# ProPrj.net
KiCad netlist of a schematic drawn in EasyEDA Pro
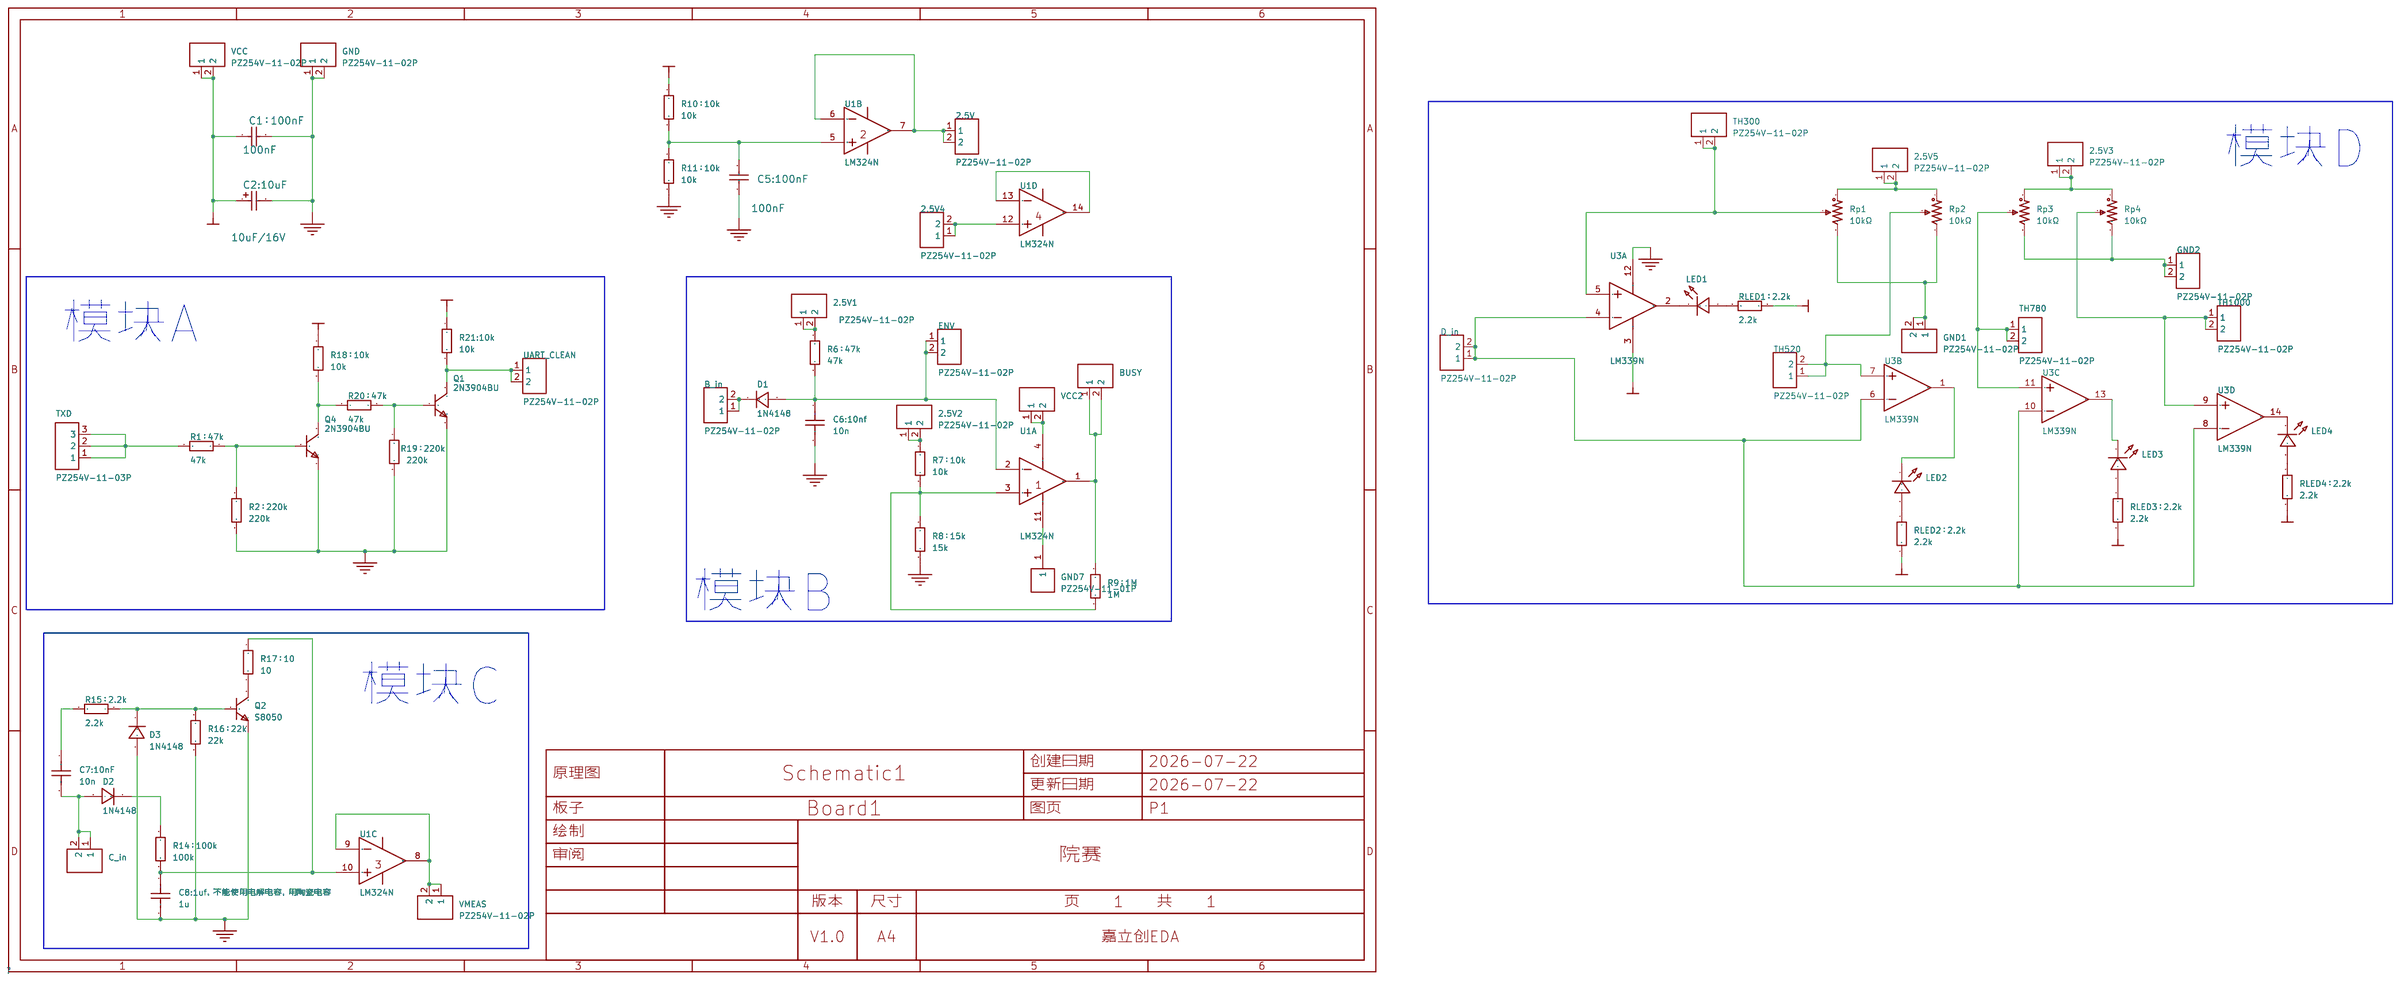
[diagram p0: schematic sheet]

(export (version "E")
  (design (tool "Eeschema 10.0.6"))
  (components
    (comp (ref "2.5V")
      (value "PZ254V-11-02P")
      (footprint "easyedapro:HDR-TH_2P-P2.54-V-M")
      (fields (field (name "Manufacturer") "XFCN(兴飞)"))
      (libsource (lib "easyedapro") (part "PZ254V-11-02P"))
    )
    (comp (ref "2.5V1")
      (value "PZ254V-11-02P")
      (footprint "easyedapro:HDR-TH_2P-P2.54-V-M")
      (fields (field (name "Manufacturer") "XFCN(兴飞)"))
      (libsource (lib "easyedapro") (part "PZ254V-11-02P"))
    )
    (comp (ref "2.5V2")
      (value "PZ254V-11-02P")
      (footprint "easyedapro:HDR-TH_2P-P2.54-V-M")
      (fields (field (name "Manufacturer") "XFCN(兴飞)"))
      (libsource (lib "easyedapro") (part "PZ254V-11-02P"))
    )
    (comp (ref "2.5V3")
      (value "PZ254V-11-02P")
      (footprint "easyedapro:HDR-TH_2P-P2.54-V-M")
      (fields (field (name "Manufacturer") "XFCN(兴飞)"))
      (libsource (lib "easyedapro") (part "PZ254V-11-02P"))
    )
    (comp (ref "2.5V4")
      (value "PZ254V-11-02P")
      (footprint "easyedapro:HDR-TH_2P-P2.54-V-M")
      (fields (field (name "Manufacturer") "XFCN(兴飞)"))
      (libsource (lib "easyedapro") (part "PZ254V-11-02P"))
    )
    (comp (ref "2.5V5")
      (value "PZ254V-11-02P")
      (footprint "easyedapro:HDR-TH_2P-P2.54-V-M")
      (fields (field (name "Manufacturer") "XFCN(兴飞)"))
      (libsource (lib "easyedapro") (part "PZ254V-11-02P"))
    )
    (comp (ref "BUSY")
      (value "PZ254V-11-02P")
      (footprint "easyedapro:HDR-TH_2P-P2.54-V-M")
      (fields (field (name "Manufacturer") "XFCN(兴飞)"))
      (libsource (lib "easyedapro") (part "PZ254V-11-02P"))
    )
    (comp (ref "B_in")
      (value "PZ254V-11-02P")
      (footprint "easyedapro:HDR-TH_2P-P2.54-V-M")
      (fields (field (name "Manufacturer") "XFCN(兴飞)"))
      (libsource (lib "easyedapro") (part "PZ254V-11-02P"))
    )
    (comp (ref "C1：100nF")
      (value "100nF")
      (footprint "easyedapro:0805")
      (description "Capacitor")
      (fields (field (name "Publisher") "Altium Limited"))
      (libsource (lib "easyedapro") (part "Cap"))
    )
    (comp (ref "C2:10uF")
      (value "10uF/16V")
      (footprint "easyedapro:P1210")
      (description "Polarized Capacitor (Radial)")
      (fields (field (name "Publisher") "Altium Limited"))
      (libsource (lib "easyedapro") (part "Cap Pol1"))
    )
    (comp (ref "C5:100nF")
      (value "100nF")
      (footprint "easyedapro:0805")
      (description "Capacitor")
      (fields (field (name "Publisher") "Altium Limited"))
      (libsource (lib "easyedapro") (part "Cap"))
    )
    (comp (ref "C6:10nf")
      (value "10n")
      (footprint "easyedapro:CAP-TH_L8.5-W5.0-P5.00-D1.2")
      (description "容值:100nF;精度:±10%;额定电压:50V;温度系数:X7R;")
      (fields (field (name "Manufacturer Part") "CT4-0805B104K500F3") (field (name "Manufacturer") "FH(风华)"))
      (libsource (lib "easyedapro") (part "CT4-0805B104K500F3"))
    )
    (comp (ref "C7:10nF")
      (value "10n")
      (footprint "easyedapro:CAP-TH_L8.5-W5.0-P5.00-D1.2")
      (description "容值:100nF;精度:±10%;额定电压:50V;温度系数:X7R;")
      (fields (field (name "Manufacturer Part") "CT4-0805B104K500F3") (field (name "Manufacturer") "FH(风华)"))
      (libsource (lib "easyedapro") (part "CT4-0805B104K500F3"))
    )
    (comp (ref "C8:1uf，不能使用电解电容，用陶瓷电容")
      (value "1u")
      (footprint "easyedapro:CAP-TH_L8.5-W5.0-P5.00-D1.2")
      (description "容值:100nF;精度:±10%;额定电压:50V;温度系数:X7R;")
      (fields (field (name "Manufacturer Part") "CT4-0805B104K500F3") (field (name "Manufacturer") "FH(风华)"))
      (libsource (lib "easyedapro") (part "CT4-0805B104K500F3"))
    )
    (comp (ref "C_in")
      (value "PZ254V-11-02P")
      (footprint "easyedapro:HDR-TH_2P-P2.54-V-M")
      (fields (field (name "Manufacturer") "XFCN(兴飞)"))
      (libsource (lib "easyedapro") (part "PZ254V-11-02P"))
    )
    (comp (ref "D1")
      (value "1N4148")
      (footprint "easyedapro:DO-35_BD2.0-L4.2-P8.20-D0.5-RD")
      (description "二极管配置:-;正向压降(Vf):1V@10mA;直流反向耐压(Vr):75V;整流电流:150mA;反向恢复时间(Trr):4ns;")
      (fields (field (name "Manufacturer") "LGE(鲁光)"))
      (libsource (lib "easyedapro") (part "1N4148_C402212"))
    )
    (comp (ref "D2")
      (value "1N4148")
      (footprint "easyedapro:DO-35_BD2.0-L4.2-P8.20-D0.5-RD")
      (description "二极管配置:-;正向压降(Vf):1V@10mA;直流反向耐压(Vr):75V;整流电流:150mA;反向恢复时间(Trr):4ns;")
      (fields (field (name "Manufacturer") "LGE(鲁光)"))
      (libsource (lib "easyedapro") (part "1N4148_C402212"))
    )
    (comp (ref "D3")
      (value "1N4148")
      (footprint "easyedapro:DO-35_BD2.0-L4.2-P8.20-D0.5-RD")
      (description "二极管配置:-;正向压降(Vf):1V@10mA;直流反向耐压(Vr):75V;整流电流:150mA;反向恢复时间(Trr):4ns;")
      (fields (field (name "Manufacturer") "LGE(鲁光)"))
      (libsource (lib "easyedapro") (part "1N4148_C402212"))
    )
    (comp (ref "D_in")
      (value "PZ254V-11-02P")
      (footprint "easyedapro:HDR-TH_2P-P2.54-V-M")
      (fields (field (name "Manufacturer") "XFCN(兴飞)"))
      (libsource (lib "easyedapro") (part "PZ254V-11-02P"))
    )
    (comp (ref "ENV")
      (value "PZ254V-11-02P")
      (footprint "easyedapro:HDR-TH_2P-P2.54-V-M")
      (fields (field (name "Manufacturer") "XFCN(兴飞)"))
      (libsource (lib "easyedapro") (part "PZ254V-11-02P"))
    )
    (comp (ref "GND")
      (value "PZ254V-11-02P")
      (footprint "easyedapro:HDR-TH_2P-P2.54-V-M")
      (fields (field (name "Manufacturer") "XFCN(兴飞)"))
      (libsource (lib "easyedapro") (part "PZ254V-11-02P"))
    )
    (comp (ref "GND1")
      (value "PZ254V-11-02P")
      (footprint "easyedapro:HDR-TH_2P-P2.54-V-M")
      (fields (field (name "Manufacturer") "XFCN(兴飞)"))
      (libsource (lib "easyedapro") (part "PZ254V-11-02P"))
    )
    (comp (ref "GND2")
      (value "PZ254V-11-02P")
      (footprint "easyedapro:HDR-TH_2P-P2.54-V-M")
      (fields (field (name "Manufacturer") "XFCN(兴飞)"))
      (libsource (lib "easyedapro") (part "PZ254V-11-02P"))
    )
    (comp (ref "GND7")
      (value "PZ254V-11-01P")
      (footprint "easyedapro:HDR-TH_1P-P2.54-V-M")
      (fields (field (name "Manufacturer") "XFCN(兴飞)"))
      (libsource (lib "easyedapro") (part "PZ254V-11-01P"))
    )
    (comp (ref "LED1")
      (value "WP1533BQ/ID")
      (footprint "easyedapro:LED-TH_2P-L13.5-W5.9-P2.54_WP1533BQ")
      (fields (field (name "Manufacturer") "Kingbright"))
      (libsource (lib "easyedapro") (part "WP1533BQ/ID"))
    )
    (comp (ref "LED2")
      (value "WP1533BQ/ID")
      (footprint "easyedapro:LED-TH_2P-L13.5-W5.9-P2.54_WP1533BQ")
      (fields (field (name "Manufacturer") "Kingbright"))
      (libsource (lib "easyedapro") (part "WP1533BQ/ID"))
    )
    (comp (ref "LED3")
      (value "WP1533BQ/ID")
      (footprint "easyedapro:LED-TH_2P-L13.5-W5.9-P2.54_WP1533BQ")
      (fields (field (name "Manufacturer") "Kingbright"))
      (libsource (lib "easyedapro") (part "WP1533BQ/ID"))
    )
    (comp (ref "LED4")
      (value "WP1533BQ/ID")
      (footprint "easyedapro:LED-TH_2P-L13.5-W5.9-P2.54_WP1533BQ")
      (fields (field (name "Manufacturer") "Kingbright"))
      (libsource (lib "easyedapro") (part "WP1533BQ/ID"))
    )
    (comp (ref "Q1")
      (value "2N3904BU")
      (footprint "easyedapro:TO-92-3_L5.1-W4.1-P1.27-L")
      (fields (field (name "Manufacturer") "onsemi(安森美)"))
      (libsource (lib "easyedapro") (part "2N3904BU"))
    )
    (comp (ref "Q2")
      (value "S8050")
      (footprint "easyedapro:SOT-23-3_L2.9-W1.3-P1.90-LS2.3-BR")
      (fields (field (name "Manufacturer") "R+O(宏嘉诚)"))
      (libsource (lib "easyedapro") (part "S8050_C20069125"))
    )
    (comp (ref "Q4")
      (value "2N3904BU")
      (footprint "easyedapro:TO-92-3_L5.1-W4.1-P1.27-L")
      (fields (field (name "Manufacturer") "onsemi(安森美)"))
      (libsource (lib "easyedapro") (part "2N3904BU"))
    )
    (comp (ref "R1：47k")
      (value "47k")
      (footprint "easyedapro:R0603")
      (libsource (lib "easyedapro") (part "电阻"))
    )
    (comp (ref "R2：220k")
      (value "220k")
      (footprint "easyedapro:R0603")
      (libsource (lib "easyedapro") (part "电阻"))
    )
    (comp (ref "R6：47k")
      (value "47k")
      (footprint "easyedapro:R0603")
      (libsource (lib "easyedapro") (part "电阻"))
    )
    (comp (ref "R7：10k")
      (value "10k")
      (footprint "easyedapro:R0603")
      (libsource (lib "easyedapro") (part "电阻"))
    )
    (comp (ref "R8：15k")
      (value "15k")
      (footprint "easyedapro:R0603")
      (libsource (lib "easyedapro") (part "电阻"))
    )
    (comp (ref "R9：1M")
      (value "1M")
      (footprint "easyedapro:R0603")
      (libsource (lib "easyedapro") (part "电阻"))
    )
    (comp (ref "R10：10k")
      (value "10k")
      (footprint "easyedapro:R0603")
      (libsource (lib "easyedapro") (part "电阻"))
    )
    (comp (ref "R11：10k")
      (value "10k")
      (footprint "easyedapro:R0603")
      (libsource (lib "easyedapro") (part "电阻"))
    )
    (comp (ref "R14：100k")
      (value "100k")
      (footprint "easyedapro:R0603")
      (libsource (lib "easyedapro") (part "电阻"))
    )
    (comp (ref "R15：2.2k")
      (value "2.2k")
      (footprint "easyedapro:R0603")
      (libsource (lib "easyedapro") (part "电阻"))
    )
    (comp (ref "R16：22k")
      (value "22k")
      (footprint "easyedapro:R0603")
      (libsource (lib "easyedapro") (part "电阻"))
    )
    (comp (ref "R17：10")
      (value "10")
      (footprint "easyedapro:R0603")
      (libsource (lib "easyedapro") (part "电阻"))
    )
    (comp (ref "R18：10k")
      (value "10k")
      (footprint "easyedapro:R0603")
      (libsource (lib "easyedapro") (part "电阻"))
    )
    (comp (ref "R19：220k")
      (value "220k")
      (footprint "easyedapro:R0603")
      (libsource (lib "easyedapro") (part "电阻"))
    )
    (comp (ref "R20：47k")
      (value "47k")
      (footprint "easyedapro:R0603")
      (libsource (lib "easyedapro") (part "电阻"))
    )
    (comp (ref "R21:10k")
      (value "10k")
      (footprint "easyedapro:R0603")
      (libsource (lib "easyedapro") (part "电阻"))
    )
    (comp (ref "RLED1：2.2k")
      (value "2.2k")
      (footprint "easyedapro:R0603")
      (libsource (lib "easyedapro") (part "电阻"))
    )
    (comp (ref "RLED2：2.2k")
      (value "2.2k")
      (footprint "easyedapro:R0603")
      (libsource (lib "easyedapro") (part "电阻"))
    )
    (comp (ref "RLED3：2.2k")
      (value "2.2k")
      (footprint "easyedapro:R0603")
      (libsource (lib "easyedapro") (part "电阻"))
    )
    (comp (ref "RLED4：2.2k")
      (value "2.2k")
      (footprint "easyedapro:R0603")
      (libsource (lib "easyedapro") (part "电阻"))
    )
    (comp (ref "Rp1")
      (value "10kΩ")
      (footprint "easyedapro:RES-ADJ-TH_3P-L10.0-W10.0-P2.50-L")
      (description "阻值:10kΩ;精度:±10%;")
      (fields (field (name "Manufacturer Part") "3296W-1-103") (field (name "Manufacturer") "BOCHEN(博晨)"))
      (libsource (lib "easyedapro") (part "3296W-1-103"))
    )
    (comp (ref "Rp2")
      (value "10kΩ")
      (footprint "easyedapro:RES-ADJ-TH_3P-L10.0-W10.0-P2.50-L")
      (description "阻值:10kΩ;精度:±10%;")
      (fields (field (name "Manufacturer Part") "3296W-1-103") (field (name "Manufacturer") "BOCHEN(博晨)"))
      (libsource (lib "easyedapro") (part "3296W-1-103"))
    )
    (comp (ref "Rp3")
      (value "10kΩ")
      (footprint "easyedapro:RES-ADJ-TH_3P-L10.0-W10.0-P2.50-L")
      (description "阻值:10kΩ;精度:±10%;")
      (fields (field (name "Manufacturer Part") "3296W-1-103") (field (name "Manufacturer") "BOCHEN(博晨)"))
      (libsource (lib "easyedapro") (part "3296W-1-103"))
    )
    (comp (ref "Rp4")
      (value "10kΩ")
      (footprint "easyedapro:RES-ADJ-TH_3P-L10.0-W10.0-P2.50-L")
      (description "阻值:10kΩ;精度:±10%;")
      (fields (field (name "Manufacturer Part") "3296W-1-103") (field (name "Manufacturer") "BOCHEN(博晨)"))
      (libsource (lib "easyedapro") (part "3296W-1-103"))
    )
    (comp (ref "TH300")
      (value "PZ254V-11-02P")
      (footprint "easyedapro:HDR-TH_2P-P2.54-V-M")
      (fields (field (name "Manufacturer") "XFCN(兴飞)"))
      (libsource (lib "easyedapro") (part "PZ254V-11-02P"))
    )
    (comp (ref "TH520")
      (value "PZ254V-11-02P")
      (footprint "easyedapro:HDR-TH_2P-P2.54-V-M")
      (fields (field (name "Manufacturer") "XFCN(兴飞)"))
      (libsource (lib "easyedapro") (part "PZ254V-11-02P"))
    )
    (comp (ref "TH780")
      (value "PZ254V-11-02P")
      (footprint "easyedapro:HDR-TH_2P-P2.54-V-M")
      (fields (field (name "Manufacturer") "XFCN(兴飞)"))
      (libsource (lib "easyedapro") (part "PZ254V-11-02P"))
    )
    (comp (ref "TH1000")
      (value "PZ254V-11-02P")
      (footprint "easyedapro:HDR-TH_2P-P2.54-V-M")
      (fields (field (name "Manufacturer") "XFCN(兴飞)"))
      (libsource (lib "easyedapro") (part "PZ254V-11-02P"))
    )
    (comp (ref "TXD")
      (value "PZ254V-11-03P")
      (footprint "easyedapro:HDR-TH_3P-P2.54-V-M_PZ254V-11-03P")
      (fields (field (name "Manufacturer") "XFCN(兴飞)"))
      (libsource (lib "easyedapro") (part "PZ254V-11-03P_C2937625"))
    )
    (comp (ref "U1")
      (value "LM324N")
      (footprint "easyedapro:DIP-14_L19.4-W6.4-P2.54-LS7.6-BL")
      (fields (field (name "Manufacturer") "HGSEMI(华冠)"))
      (libsource (lib "easyedapro") (part "LM324N_C725320"))
    )
    (comp (ref "U3")
      (value "LM339N")
      (footprint "easyedapro:PDIP-14_L19.3-W6.4-P2.54-LS9.0-BL")
      (fields (field (name "Manufacturer") "TI(德州仪器)"))
      (libsource (lib "easyedapro") (part "LM339N_C39202084"))
    )
    (comp (ref "UART_CLEAN")
      (value "PZ254V-11-02P")
      (footprint "easyedapro:HDR-TH_2P-P2.54-V-M")
      (fields (field (name "Manufacturer") "XFCN(兴飞)"))
      (libsource (lib "easyedapro") (part "PZ254V-11-02P"))
    )
    (comp (ref "VCC")
      (value "PZ254V-11-02P")
      (footprint "easyedapro:HDR-TH_2P-P2.54-V-M")
      (fields (field (name "Manufacturer") "XFCN(兴飞)"))
      (libsource (lib "easyedapro") (part "PZ254V-11-02P"))
    )
    (comp (ref "VCC2")
      (value "PZ254V-11-02P")
      (footprint "easyedapro:HDR-TH_2P-P2.54-V-M")
      (fields (field (name "Manufacturer") "XFCN(兴飞)"))
      (libsource (lib "easyedapro") (part "PZ254V-11-02P"))
    )
    (comp (ref "VMEAS")
      (value "PZ254V-11-02P")
      (footprint "easyedapro:HDR-TH_2P-P2.54-V-M")
      (fields (field (name "Manufacturer") "XFCN(兴飞)"))
      (libsource (lib "easyedapro") (part "PZ254V-11-02P"))
    )
  )
  (nets
    (net (code "1") (name "GND") (class "Default")
      (node (ref "C1：100nF") (pin "2") (pinfunction "2_2") (pintype "unspecified"))
      (node (ref "C2:10uF") (pin "2") (pinfunction "2_2") (pintype "unspecified"))
      (node (ref "C5:100nF") (pin "1") (pinfunction "1_1") (pintype "unspecified"))
      (node (ref "C6:10nf") (pin "2") (pinfunction "2_2") (pintype "unspecified"))
      (node (ref "C8:1uf，不能使用电解电容，用陶瓷电容") (pin "2") (pinfunction "2_2") (pintype "unspecified"))
      (node (ref "D3") (pin "2") (pinfunction "A_2") (pintype "unspecified"))
      (node (ref "GND") (pin "1") (pinfunction "1_1") (pintype "unspecified"))
      (node (ref "GND") (pin "2") (pinfunction "2_2") (pintype "unspecified"))
      (node (ref "Q1") (pin "1") (pinfunction "E_1") (pintype "input"))
      (node (ref "Q2") (pin "2") (pinfunction "E_2") (pintype "input"))
      (node (ref "Q4") (pin "1") (pinfunction "E_1") (pintype "input"))
      (node (ref "R11：10k") (pin "2") (pinfunction "2_2") (pintype "input"))
      (node (ref "R16：22k") (pin "2") (pinfunction "2_2") (pintype "input"))
      (node (ref "R19：220k") (pin "2") (pinfunction "2_2") (pintype "input"))
      (node (ref "R2：220k") (pin "2") (pinfunction "2_2") (pintype "input"))
      (node (ref "R8：15k") (pin "2") (pinfunction "2_2") (pintype "input"))
      (node (ref "U3") (pin "12") (pinfunction "GND_12") (pintype "unspecified"))
    )
    (net (code "2") (name "Net-(2.5V1-Pad1)") (class "Default")
      (node (ref "2.5V1") (pin "1") (pinfunction "1_1") (pintype "unspecified"))
      (node (ref "2.5V1") (pin "2") (pinfunction "2_2") (pintype "unspecified"))
      (node (ref "R6：47k") (pin "1") (pinfunction "1_1") (pintype "input"))
    )
    (net (code "3") (name "Net-(2.5V2-Pad1)") (class "Default")
      (node (ref "2.5V2") (pin "1") (pinfunction "1_1") (pintype "unspecified"))
      (node (ref "2.5V2") (pin "2") (pinfunction "2_2") (pintype "unspecified"))
      (node (ref "R7：10k") (pin "1") (pinfunction "1_1") (pintype "input"))
    )
    (net (code "4") (name "Net-(2.5V3-Pad1)") (class "Default")
      (node (ref "2.5V3") (pin "1") (pinfunction "1_1") (pintype "unspecified"))
      (node (ref "2.5V3") (pin "2") (pinfunction "2_2") (pintype "unspecified"))
      (node (ref "Rp3") (pin "1") (pinfunction "1_1") (pintype "unspecified"))
      (node (ref "Rp4") (pin "1") (pinfunction "1_1") (pintype "unspecified"))
    )
    (net (code "5") (name "Net-(2.5V5-Pad1)") (class "Default")
      (node (ref "2.5V5") (pin "1") (pinfunction "1_1") (pintype "unspecified"))
      (node (ref "2.5V5") (pin "2") (pinfunction "2_2") (pintype "unspecified"))
      (node (ref "Rp1") (pin "1") (pinfunction "1_1") (pintype "unspecified"))
      (node (ref "Rp2") (pin "1") (pinfunction "1_1") (pintype "unspecified"))
    )
    (net (code "6") (name "Net-(C7:10nF-Pad1)") (class "Default")
      (node (ref "C7:10nF") (pin "1") (pinfunction "1_1") (pintype "unspecified"))
      (node (ref "R15：2.2k") (pin "2") (pinfunction "2_2") (pintype "input"))
    )
    (net (code "7") (name "Net-(D1-A)") (class "Default")
      (node (ref "C6:10nf") (pin "1") (pinfunction "1_1") (pintype "unspecified"))
      (node (ref "D1") (pin "2") (pinfunction "A_2") (pintype "unspecified"))
      (node (ref "ENV") (pin "1") (pinfunction "1_1") (pintype "unspecified"))
      (node (ref "ENV") (pin "2") (pinfunction "2_2") (pintype "unspecified"))
      (node (ref "R6：47k") (pin "2") (pinfunction "2_2") (pintype "input"))
      (node (ref "U1") (pin "2") (pinfunction "IN1-_2") (pintype "unspecified"))
    )
    (net (code "8") (name "Net-(D1-C)") (class "Default")
      (node (ref "B_in") (pin "1") (pinfunction "1_1") (pintype "unspecified"))
      (node (ref "B_in") (pin "2") (pinfunction "2_2") (pintype "unspecified"))
      (node (ref "D1") (pin "1") (pinfunction "C_1") (pintype "unspecified"))
    )
    (net (code "9") (name "Net-(D2-A)") (class "Default")
      (node (ref "C7:10nF") (pin "2") (pinfunction "2_2") (pintype "unspecified"))
      (node (ref "C_in") (pin "1") (pinfunction "1_1") (pintype "unspecified"))
      (node (ref "C_in") (pin "2") (pinfunction "2_2") (pintype "unspecified"))
      (node (ref "D2") (pin "2") (pinfunction "A_2") (pintype "unspecified"))
    )
    (net (code "10") (name "Net-(D2-C)") (class "Default")
      (node (ref "D2") (pin "1") (pinfunction "C_1") (pintype "unspecified"))
      (node (ref "R14：100k") (pin "1") (pinfunction "1_1") (pintype "input"))
    )
    (net (code "11") (name "Net-(D3-C)") (class "Default")
      (node (ref "D3") (pin "1") (pinfunction "C_1") (pintype "unspecified"))
      (node (ref "Q2") (pin "1") (pinfunction "B_1") (pintype "input"))
      (node (ref "R15：2.2k") (pin "1") (pinfunction "1_1") (pintype "input"))
      (node (ref "R16：22k") (pin "1") (pinfunction "1_1") (pintype "input"))
    )
    (net (code "12") (name "Net-(GND1-Pad1)") (class "Default")
      (node (ref "GND1") (pin "1") (pinfunction "1_1") (pintype "unspecified"))
      (node (ref "GND1") (pin "2") (pinfunction "2_2") (pintype "unspecified"))
      (node (ref "Rp1") (pin "3") (pinfunction "3_3") (pintype "unspecified"))
      (node (ref "Rp2") (pin "3") (pinfunction "3_3") (pintype "unspecified"))
    )
    (net (code "13") (name "Net-(GND2-Pad1)") (class "Default")
      (node (ref "GND2") (pin "1") (pinfunction "1_1") (pintype "unspecified"))
      (node (ref "GND2") (pin "2") (pinfunction "2_2") (pintype "unspecified"))
      (node (ref "Rp3") (pin "3") (pinfunction "3_3") (pintype "unspecified"))
      (node (ref "Rp4") (pin "3") (pinfunction "3_3") (pintype "unspecified"))
    )
    (net (code "14") (name "Net-(LED1-A)") (class "Default")
      (node (ref "LED1") (pin "2") (pinfunction "A_2") (pintype "unspecified"))
      (node (ref "RLED1：2.2k") (pin "2") (pinfunction "2_2") (pintype "input"))
    )
    (net (code "15") (name "Net-(LED1-C)") (class "Default")
      (node (ref "LED1") (pin "1") (pinfunction "C_1") (pintype "unspecified"))
      (node (ref "U3") (pin "2") (pinfunction "OUT_2") (pintype "unspecified"))
    )
    (net (code "16") (name "Net-(LED2-A)") (class "Default")
      (node (ref "LED2") (pin "2") (pinfunction "A_2") (pintype "unspecified"))
      (node (ref "RLED2：2.2k") (pin "1") (pinfunction "1_1") (pintype "input"))
    )
    (net (code "17") (name "Net-(LED2-C)") (class "Default")
      (node (ref "LED2") (pin "1") (pinfunction "C_1") (pintype "unspecified"))
      (node (ref "U3") (pin "1") (pinfunction "OUT_1") (pintype "unspecified"))
    )
    (net (code "18") (name "Net-(LED3-A)") (class "Default")
      (node (ref "LED3") (pin "2") (pinfunction "A_2") (pintype "unspecified"))
      (node (ref "RLED3：2.2k") (pin "1") (pinfunction "1_1") (pintype "input"))
    )
    (net (code "19") (name "Net-(LED3-C)") (class "Default")
      (node (ref "LED3") (pin "1") (pinfunction "C_1") (pintype "unspecified"))
      (node (ref "U3") (pin "13") (pinfunction "OUT_13") (pintype "unspecified"))
    )
    (net (code "20") (name "Net-(LED4-A)") (class "Default")
      (node (ref "LED4") (pin "2") (pinfunction "A_2") (pintype "unspecified"))
      (node (ref "RLED4：2.2k") (pin "1") (pinfunction "1_1") (pintype "input"))
    )
    (net (code "21") (name "Net-(LED4-C)") (class "Default")
      (node (ref "LED4") (pin "1") (pinfunction "C_1") (pintype "unspecified"))
      (node (ref "U3") (pin "14") (pinfunction "OUT_14") (pintype "unspecified"))
    )
    (net (code "22") (name "Net-(Q1-B)") (class "Default")
      (node (ref "Q1") (pin "2") (pinfunction "B_2") (pintype "input"))
      (node (ref "R19：220k") (pin "1") (pinfunction "1_1") (pintype "input"))
      (node (ref "R20：47k") (pin "2") (pinfunction "2_2") (pintype "input"))
    )
    (net (code "23") (name "Net-(Q1-C)") (class "Default")
      (node (ref "Q1") (pin "3") (pinfunction "C_3") (pintype "input"))
      (node (ref "R21:10k") (pin "2") (pinfunction "2_2") (pintype "input"))
      (node (ref "UART_CLEAN") (pin "1") (pinfunction "1_1") (pintype "unspecified"))
      (node (ref "UART_CLEAN") (pin "2") (pinfunction "2_2") (pintype "unspecified"))
    )
    (net (code "24") (name "Net-(Q2-C)") (class "Default")
      (node (ref "Q2") (pin "3") (pinfunction "C_3") (pintype "input"))
      (node (ref "R17：10") (pin "2") (pinfunction "2_2") (pintype "input"))
    )
    (net (code "25") (name "Net-(Q4-B)") (class "Default")
      (node (ref "Q4") (pin "2") (pinfunction "B_2") (pintype "input"))
      (node (ref "R1：47k") (pin "1") (pinfunction "1_1") (pintype "input"))
      (node (ref "R2：220k") (pin "1") (pinfunction "1_1") (pintype "input"))
    )
    (net (code "26") (name "Net-(Q4-C)") (class "Default")
      (node (ref "Q4") (pin "3") (pinfunction "C_3") (pintype "input"))
      (node (ref "R18：10k") (pin "2") (pinfunction "2_2") (pintype "input"))
      (node (ref "R20：47k") (pin "1") (pinfunction "1_1") (pintype "input"))
    )
    (net (code "27") (name "Net-(R1：47k-Pad2)") (class "Default")
      (node (ref "R1：47k") (pin "2") (pinfunction "2_2") (pintype "input"))
      (node (ref "TXD") (pin "1") (pinfunction "1_1") (pintype "unspecified"))
      (node (ref "TXD") (pin "2") (pinfunction "2_2") (pintype "unspecified"))
      (node (ref "TXD") (pin "3") (pinfunction "3_3") (pintype "unspecified"))
    )
    (net (code "28") (name "Net-(U1A-GND)") (class "Default")
      (node (ref "GND7") (pin "1") (pinfunction "1_1") (pintype "unspecified"))
      (node (ref "U1") (pin "11") (pinfunction "GND_11") (pintype "unspecified"))
    )
    (net (code "29") (name "Net-(U1A-IN1+)") (class "Default")
      (node (ref "R7：10k") (pin "2") (pinfunction "2_2") (pintype "input"))
      (node (ref "R8：15k") (pin "1") (pinfunction "1_1") (pintype "input"))
      (node (ref "R9：1M") (pin "1") (pinfunction "1_1") (pintype "input"))
      (node (ref "U1") (pin "3") (pinfunction "IN1+_3") (pintype "unspecified"))
    )
    (net (code "30") (name "Net-(U1A-OUT1)") (class "Default")
      (node (ref "BUSY") (pin "1") (pinfunction "1_1") (pintype "unspecified"))
      (node (ref "BUSY") (pin "2") (pinfunction "2_2") (pintype "unspecified"))
      (node (ref "R9：1M") (pin "2") (pinfunction "2_2") (pintype "input"))
      (node (ref "U1") (pin "1") (pinfunction "OUT1_1") (pintype "output"))
    )
    (net (code "31") (name "Net-(U1A-VCC)") (class "Default")
      (node (ref "U1") (pin "4") (pinfunction "VCC_4") (pintype "unspecified"))
      (node (ref "VCC2") (pin "1") (pinfunction "1_1") (pintype "unspecified"))
      (node (ref "VCC2") (pin "2") (pinfunction "2_2") (pintype "unspecified"))
    )
    (net (code "32") (name "Net-(U1B-IN2+)") (class "Default")
      (node (ref "C5:100nF") (pin "2") (pinfunction "2_2") (pintype "unspecified"))
      (node (ref "R10：10k") (pin "2") (pinfunction "2_2") (pintype "input"))
      (node (ref "R11：10k") (pin "1") (pinfunction "1_1") (pintype "input"))
      (node (ref "U1") (pin "5") (pinfunction "IN2+_5") (pintype "unspecified"))
    )
    (net (code "33") (name "Net-(U1B-IN2-)") (class "Default")
      (node (ref "2.5V") (pin "1") (pinfunction "1_1") (pintype "unspecified"))
      (node (ref "2.5V") (pin "2") (pinfunction "2_2") (pintype "unspecified"))
      (node (ref "U1") (pin "6") (pinfunction "IN2-_6") (pintype "unspecified"))
      (node (ref "U1") (pin "7") (pinfunction "OUT2_7") (pintype "output"))
    )
    (net (code "34") (name "Net-(U1C-IN3+)") (class "Default")
      (node (ref "C8:1uf，不能使用电解电容，用陶瓷电容") (pin "1") (pinfunction "1_1") (pintype "unspecified"))
      (node (ref "R14：100k") (pin "2") (pinfunction "2_2") (pintype "input"))
      (node (ref "R17：10") (pin "1") (pinfunction "1_1") (pintype "input"))
      (node (ref "U1") (pin "10") (pinfunction "IN3+_10") (pintype "unspecified"))
    )
    (net (code "35") (name "Net-(U1C-IN3-)") (class "Default")
      (node (ref "U1") (pin "8") (pinfunction "OUT3_8") (pintype "output"))
      (node (ref "U1") (pin "9") (pinfunction "IN3-_9") (pintype "unspecified"))
      (node (ref "VMEAS") (pin "1") (pinfunction "1_1") (pintype "unspecified"))
      (node (ref "VMEAS") (pin "2") (pinfunction "2_2") (pintype "unspecified"))
    )
    (net (code "36") (name "Net-(U1D-IN4+)") (class "Default")
      (node (ref "2.5V4") (pin "1") (pinfunction "1_1") (pintype "unspecified"))
      (node (ref "2.5V4") (pin "2") (pinfunction "2_2") (pintype "unspecified"))
      (node (ref "U1") (pin "12") (pinfunction "IN4+_12") (pintype "unspecified"))
    )
    (net (code "37") (name "Net-(U1D-IN4-)") (class "Default")
      (node (ref "U1") (pin "13") (pinfunction "IN4-_13") (pintype "unspecified"))
      (node (ref "U1") (pin "14") (pinfunction "OUT4_14") (pintype "output"))
    )
    (net (code "38") (name "Net-(U3A-IN+)") (class "Default")
      (node (ref "Rp1") (pin "2") (pinfunction "2_2") (pintype "unspecified"))
      (node (ref "TH300") (pin "1") (pinfunction "1_1") (pintype "unspecified"))
      (node (ref "TH300") (pin "2") (pinfunction "2_2") (pintype "unspecified"))
      (node (ref "U3") (pin "5") (pinfunction "IN+_5") (pintype "unspecified"))
    )
    (net (code "39") (name "Net-(U3A-IN-)") (class "Default")
      (node (ref "D_in") (pin "1") (pinfunction "1_1") (pintype "unspecified"))
      (node (ref "D_in") (pin "2") (pinfunction "2_2") (pintype "unspecified"))
      (node (ref "U3") (pin "10") (pinfunction "IN-_10") (pintype "unspecified"))
      (node (ref "U3") (pin "4") (pinfunction "IN-_4") (pintype "unspecified"))
      (node (ref "U3") (pin "6") (pinfunction "IN-_6") (pintype "unspecified"))
      (node (ref "U3") (pin "8") (pinfunction "IN-_8") (pintype "unspecified"))
    )
    (net (code "40") (name "Net-(U3B-IN+)") (class "Default")
      (node (ref "Rp2") (pin "2") (pinfunction "2_2") (pintype "unspecified"))
      (node (ref "TH520") (pin "1") (pinfunction "1_1") (pintype "unspecified"))
      (node (ref "TH520") (pin "2") (pinfunction "2_2") (pintype "unspecified"))
      (node (ref "U3") (pin "7") (pinfunction "IN+_7") (pintype "unspecified"))
    )
    (net (code "41") (name "Net-(U3C-IN+)") (class "Default")
      (node (ref "Rp3") (pin "2") (pinfunction "2_2") (pintype "unspecified"))
      (node (ref "TH780") (pin "1") (pinfunction "1_1") (pintype "unspecified"))
      (node (ref "TH780") (pin "2") (pinfunction "2_2") (pintype "unspecified"))
      (node (ref "U3") (pin "11") (pinfunction "IN+_11") (pintype "unspecified"))
    )
    (net (code "42") (name "Net-(U3D-IN+)") (class "Default")
      (node (ref "Rp4") (pin "2") (pinfunction "2_2") (pintype "unspecified"))
      (node (ref "TH1000") (pin "1") (pinfunction "1_1") (pintype "unspecified"))
      (node (ref "TH1000") (pin "2") (pinfunction "2_2") (pintype "unspecified"))
      (node (ref "U3") (pin "9") (pinfunction "IN+_9") (pintype "unspecified"))
    )
    (net (code "43") (name "VCC") (class "Default")
      (node (ref "C1：100nF") (pin "1") (pinfunction "1_1") (pintype "unspecified"))
      (node (ref "C2:10uF") (pin "1") (pinfunction "1_1") (pintype "unspecified"))
      (node (ref "R10：10k") (pin "1") (pinfunction "1_1") (pintype "input"))
      (node (ref "R18：10k") (pin "1") (pinfunction "1_1") (pintype "input"))
      (node (ref "R21:10k") (pin "1") (pinfunction "1_1") (pintype "input"))
      (node (ref "RLED1：2.2k") (pin "1") (pinfunction "1_1") (pintype "input"))
      (node (ref "RLED2：2.2k") (pin "2") (pinfunction "2_2") (pintype "input"))
      (node (ref "RLED3：2.2k") (pin "2") (pinfunction "2_2") (pintype "input"))
      (node (ref "RLED4：2.2k") (pin "2") (pinfunction "2_2") (pintype "input"))
      (node (ref "U3") (pin "3") (pinfunction "V+_3") (pintype "unspecified"))
      (node (ref "VCC") (pin "1") (pinfunction "1_1") (pintype "unspecified"))
      (node (ref "VCC") (pin "2") (pinfunction "2_2") (pintype "unspecified"))
    )
  )
)
